# SMARTCONTROL.net
KiCad netlist of a schematic drawn in EAGLE
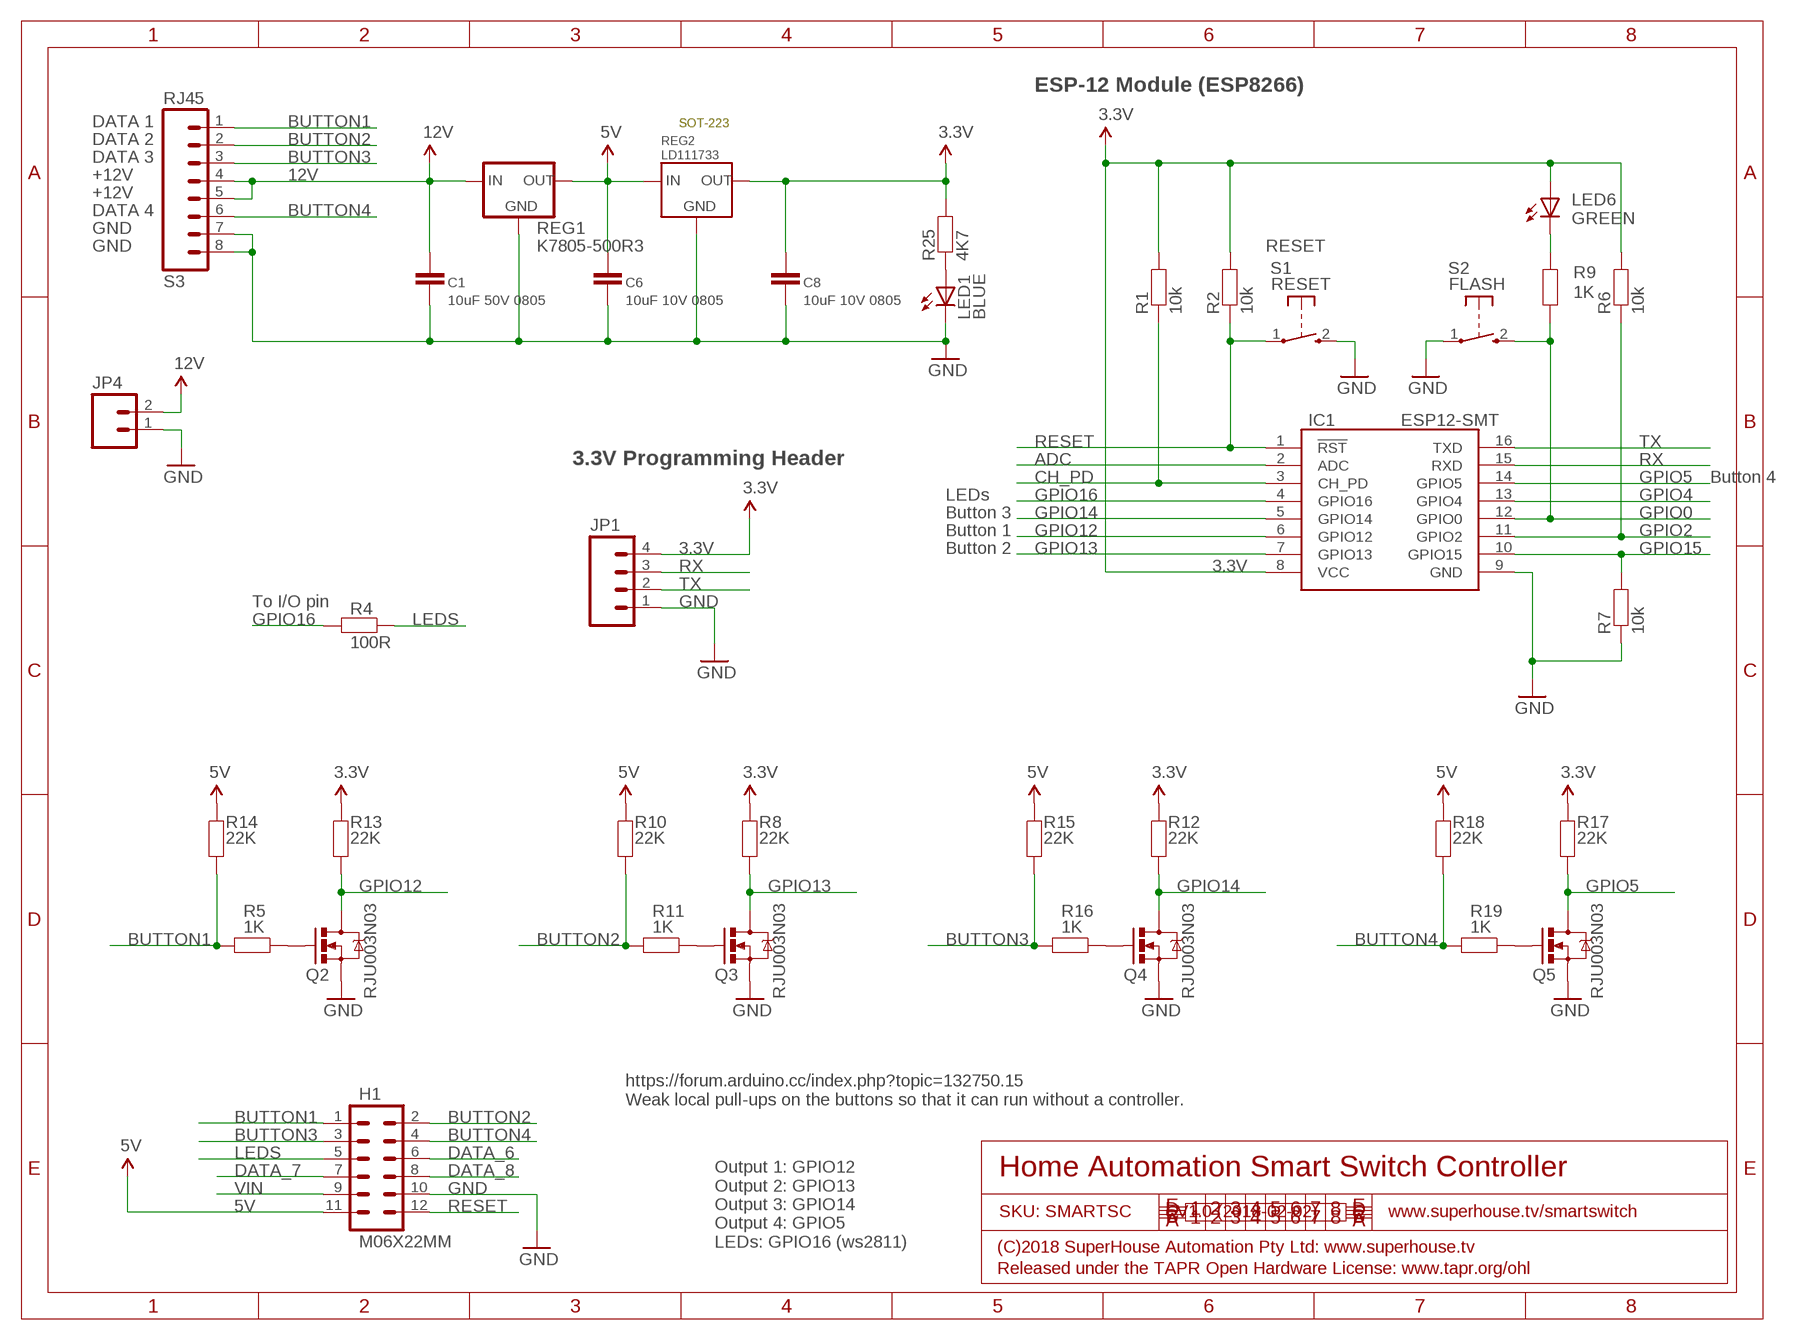
[diagram p0: schematic, sheet 1]

(export (version "E")
  (design (tool "Eeschema 10.0.6"))
  (components
    (comp (ref "C1")
      (value "10uF 50V 0805")
      (footprint "eagle-import:C0805")
      (libsource (lib "eagle-import") (part "CAP0805"))
    )
    (comp (ref "C6")
      (value "10uF 10V 0805")
      (footprint "eagle-import:C0805")
      (libsource (lib "eagle-import") (part "CAP0805"))
    )
    (comp (ref "C8")
      (value "10uF 10V 0805")
      (footprint "eagle-import:C0805")
      (libsource (lib "eagle-import") (part "CAP0805"))
    )
    (comp (ref "H1")
      (value "M06X22MM")
      (footprint "eagle-import:2X6-2MM")
      (libsource (lib "eagle-import") (part "M06X22MM"))
    )
    (comp (ref "IC1")
      (value "ESP12-SMT")
      (footprint "eagle-import:ESP12")
      (libsource (lib "eagle-import") (part "ESP12-SMT"))
    )
    (comp (ref "JP1")
      (value "M04PTH")
      (footprint "eagle-import:1X04")
      (libsource (lib "eagle-import") (part "M04PTH"))
    )
    (comp (ref "JP4")
      (value "M023.5MM")
      (footprint "eagle-import:SCREWTERMINAL-3.5MM-2")
      (libsource (lib "eagle-import") (part "M023.5MM"))
    )
    (comp (ref "LED1")
      (value "BLUE")
      (footprint "eagle-import:LED-0603")
      (libsource (lib "eagle-import") (part "LED0603"))
    )
    (comp (ref "LED6")
      (value "GREEN")
      (footprint "eagle-import:LED-0603")
      (libsource (lib "eagle-import") (part "LED0603"))
    )
    (comp (ref "Q2")
      (value "RJU003N03")
      (footprint "eagle-import:SOT32-3")
      (libsource (lib "eagle-import") (part "MOSFET-NCHANNEL-323"))
    )
    (comp (ref "Q3")
      (value "RJU003N03")
      (footprint "eagle-import:SOT32-3")
      (libsource (lib "eagle-import") (part "MOSFET-NCHANNEL-323"))
    )
    (comp (ref "Q4")
      (value "RJU003N03")
      (footprint "eagle-import:SOT32-3")
      (libsource (lib "eagle-import") (part "MOSFET-NCHANNEL-323"))
    )
    (comp (ref "Q5")
      (value "RJU003N03")
      (footprint "eagle-import:SOT32-3")
      (libsource (lib "eagle-import") (part "MOSFET-NCHANNEL-323"))
    )
    (comp (ref "R1")
      (value "10k")
      (footprint "eagle-import:R0603")
      (libsource (lib "eagle-import") (part "RESISTOR0603"))
    )
    (comp (ref "R2")
      (value "10k")
      (footprint "eagle-import:R0603")
      (libsource (lib "eagle-import") (part "RESISTOR0603"))
    )
    (comp (ref "R4")
      (value "100R")
      (footprint "eagle-import:R0603")
      (libsource (lib "eagle-import") (part "RESISTOR0603"))
    )
    (comp (ref "R5")
      (value "1K")
      (footprint "eagle-import:R0603")
      (libsource (lib "eagle-import") (part "RESISTOR0603"))
    )
    (comp (ref "R6")
      (value "10k")
      (footprint "eagle-import:R0603")
      (libsource (lib "eagle-import") (part "RESISTOR0603"))
    )
    (comp (ref "R7")
      (value "10k")
      (footprint "eagle-import:R0603")
      (libsource (lib "eagle-import") (part "RESISTOR0603"))
    )
    (comp (ref "R8")
      (value "22K")
      (footprint "eagle-import:R0603")
      (libsource (lib "eagle-import") (part "RESISTOR0603"))
    )
    (comp (ref "R9")
      (value "1K")
      (footprint "eagle-import:R0603")
      (libsource (lib "eagle-import") (part "RESISTOR0603"))
    )
    (comp (ref "R10")
      (value "22K")
      (footprint "eagle-import:R0603")
      (libsource (lib "eagle-import") (part "RESISTOR0603"))
    )
    (comp (ref "R11")
      (value "1K")
      (footprint "eagle-import:R0603")
      (libsource (lib "eagle-import") (part "RESISTOR0603"))
    )
    (comp (ref "R12")
      (value "22K")
      (footprint "eagle-import:R0603")
      (libsource (lib "eagle-import") (part "RESISTOR0603"))
    )
    (comp (ref "R13")
      (value "22K")
      (footprint "eagle-import:R0603")
      (libsource (lib "eagle-import") (part "RESISTOR0603"))
    )
    (comp (ref "R14")
      (value "22K")
      (footprint "eagle-import:R0603")
      (libsource (lib "eagle-import") (part "RESISTOR0603"))
    )
    (comp (ref "R15")
      (value "22K")
      (footprint "eagle-import:R0603")
      (libsource (lib "eagle-import") (part "RESISTOR0603"))
    )
    (comp (ref "R16")
      (value "1K")
      (footprint "eagle-import:R0603")
      (libsource (lib "eagle-import") (part "RESISTOR0603"))
    )
    (comp (ref "R17")
      (value "22K")
      (footprint "eagle-import:R0603")
      (libsource (lib "eagle-import") (part "RESISTOR0603"))
    )
    (comp (ref "R18")
      (value "22K")
      (footprint "eagle-import:R0603")
      (libsource (lib "eagle-import") (part "RESISTOR0603"))
    )
    (comp (ref "R19")
      (value "1K")
      (footprint "eagle-import:R0603")
      (libsource (lib "eagle-import") (part "RESISTOR0603"))
    )
    (comp (ref "R25")
      (value "4K7")
      (footprint "eagle-import:R0603")
      (libsource (lib "eagle-import") (part "RESISTOR0603"))
    )
    (comp (ref "REG1")
      (value "K7805-500R3")
      (footprint "eagle-import:K78XX-500R3")
      (libsource (lib "eagle-import") (part "K78XX-500R3"))
    )
    (comp (ref "REG2")
      (value "LD111733")
      (footprint "eagle-import:SOT-223")
      (libsource (lib "eagle-import") (part "LD1117"))
    )
    (comp (ref "S1")
      (value "RESET")
      (footprint "eagle-import:TACTILE_SMD_3X4X2")
      (libsource (lib "eagle-import") (part "TAC_SWITCH_2PINSMT"))
    )
    (comp (ref "S2")
      (value "FLASH")
      (footprint "eagle-import:TACTILE_SMD_3X4X2")
      (libsource (lib "eagle-import") (part "TAC_SWITCH_2PINSMT"))
    )
    (comp (ref "S3")
      (value "RJ45")
      (footprint "eagle-import:RJ45")
      (libsource (lib "eagle-import") (part "RJ45"))
    )
  )
  (nets
    (net (code "1") (name "/ADC") (class "Default")
      (node (ref "IC1") (pin "2") (pinfunction "ADC_2") (pintype "input"))
    )
    (net (code "2") (name "/BUTTON1") (class "Default")
      (node (ref "H1") (pin "1") (pinfunction "1_1") (pintype "passive"))
      (node (ref "R14") (pin "1") (pinfunction "1_1") (pintype "passive"))
      (node (ref "R5") (pin "2") (pinfunction "2_2") (pintype "passive"))
      (node (ref "S3") (pin "1") (pinfunction "1_1") (pintype "passive"))
    )
    (net (code "3") (name "/BUTTON2") (class "Default")
      (node (ref "H1") (pin "2") (pinfunction "2_2") (pintype "passive"))
      (node (ref "R10") (pin "1") (pinfunction "1_1") (pintype "passive"))
      (node (ref "R11") (pin "2") (pinfunction "2_2") (pintype "passive"))
      (node (ref "S3") (pin "2") (pinfunction "2_2") (pintype "passive"))
    )
    (net (code "4") (name "/BUTTON3") (class "Default")
      (node (ref "H1") (pin "3") (pinfunction "3_3") (pintype "passive"))
      (node (ref "R15") (pin "1") (pinfunction "1_1") (pintype "passive"))
      (node (ref "R16") (pin "2") (pinfunction "2_2") (pintype "passive"))
      (node (ref "S3") (pin "3") (pinfunction "3_3") (pintype "passive"))
    )
    (net (code "5") (name "/BUTTON4") (class "Default")
      (node (ref "H1") (pin "4") (pinfunction "4_4") (pintype "passive"))
      (node (ref "R18") (pin "1") (pinfunction "1_1") (pintype "passive"))
      (node (ref "R19") (pin "2") (pinfunction "2_2") (pintype "passive"))
      (node (ref "S3") (pin "6") (pinfunction "6_6") (pintype "passive"))
    )
    (net (code "6") (name "/CH_PD") (class "Default")
      (node (ref "IC1") (pin "3") (pinfunction "CH_PD_3") (pintype "input"))
      (node (ref "R1") (pin "1") (pinfunction "1_1") (pintype "passive"))
    )
    (net (code "7") (name "/DATA_6") (class "Default")
      (node (ref "H1") (pin "6") (pinfunction "6_6") (pintype "passive"))
    )
    (net (code "8") (name "/DATA_7") (class "Default")
      (node (ref "H1") (pin "7") (pinfunction "7_7") (pintype "passive"))
    )
    (net (code "9") (name "/DATA_8") (class "Default")
      (node (ref "H1") (pin "8") (pinfunction "8_8") (pintype "passive"))
    )
    (net (code "10") (name "/GPIO0") (class "Default")
      (node (ref "IC1") (pin "12") (pinfunction "GPIO0_12") (pintype "bidirectional"))
      (node (ref "R9") (pin "2") (pinfunction "2_2") (pintype "passive"))
      (node (ref "S2") (pin "2") (pinfunction "S_2") (pintype "passive"))
    )
    (net (code "11") (name "/GPIO2") (class "Default")
      (node (ref "IC1") (pin "11") (pinfunction "GPIO2_11") (pintype "bidirectional"))
      (node (ref "R6") (pin "1") (pinfunction "1_1") (pintype "passive"))
    )
    (net (code "12") (name "/GPIO4") (class "Default")
      (node (ref "IC1") (pin "13") (pinfunction "GPIO4_13") (pintype "bidirectional"))
    )
    (net (code "13") (name "/GPIO5") (class "Default")
      (node (ref "IC1") (pin "14") (pinfunction "GPIO5_14") (pintype "bidirectional"))
      (node (ref "Q5") (pin "3") (pinfunction "D_3") (pintype "passive"))
      (node (ref "R17") (pin "1") (pinfunction "1_1") (pintype "passive"))
    )
    (net (code "14") (name "/GPIO12") (class "Default")
      (node (ref "IC1") (pin "6") (pinfunction "GPIO12_6") (pintype "bidirectional"))
      (node (ref "Q2") (pin "3") (pinfunction "D_3") (pintype "passive"))
      (node (ref "R13") (pin "1") (pinfunction "1_1") (pintype "passive"))
    )
    (net (code "15") (name "/GPIO13") (class "Default")
      (node (ref "IC1") (pin "7") (pinfunction "GPIO13_7") (pintype "bidirectional"))
      (node (ref "Q3") (pin "3") (pinfunction "D_3") (pintype "passive"))
      (node (ref "R8") (pin "1") (pinfunction "1_1") (pintype "passive"))
    )
    (net (code "16") (name "/GPIO14") (class "Default")
      (node (ref "IC1") (pin "5") (pinfunction "GPIO14_5") (pintype "bidirectional"))
      (node (ref "Q4") (pin "3") (pinfunction "D_3") (pintype "passive"))
      (node (ref "R12") (pin "1") (pinfunction "1_1") (pintype "passive"))
    )
    (net (code "17") (name "/GPIO15") (class "Default")
      (node (ref "IC1") (pin "10") (pinfunction "GPIO15_10") (pintype "bidirectional"))
      (node (ref "R7") (pin "2") (pinfunction "2_2") (pintype "passive"))
    )
    (net (code "18") (name "/GPIO16") (class "Default")
      (node (ref "IC1") (pin "4") (pinfunction "GPIO16_4") (pintype "bidirectional"))
      (node (ref "R4") (pin "2") (pinfunction "2_2") (pintype "passive"))
    )
    (net (code "19") (name "/LEDS") (class "Default")
      (node (ref "H1") (pin "5") (pinfunction "5_5") (pintype "passive"))
      (node (ref "R4") (pin "1") (pinfunction "1_1") (pintype "passive"))
    )
    (net (code "20") (name "/RESET") (class "Default")
      (node (ref "H1") (pin "12") (pinfunction "12_12") (pintype "passive"))
      (node (ref "IC1") (pin "1") (pinfunction "~{RST}_1") (pintype "bidirectional"))
      (node (ref "R2") (pin "1") (pinfunction "1_1") (pintype "passive"))
      (node (ref "S1") (pin "1") (pinfunction "P_1") (pintype "passive"))
    )
    (net (code "21") (name "/RX") (class "Default")
      (node (ref "IC1") (pin "15") (pinfunction "RXD_15") (pintype "input"))
      (node (ref "JP1") (pin "3") (pinfunction "3_3") (pintype "passive"))
    )
    (net (code "22") (name "/TX") (class "Default")
      (node (ref "IC1") (pin "16") (pinfunction "TXD_16") (pintype "output"))
      (node (ref "JP1") (pin "2") (pinfunction "2_2") (pintype "passive"))
    )
    (net (code "23") (name "/VIN") (class "Default")
      (node (ref "H1") (pin "9") (pinfunction "9_9") (pintype "passive"))
    )
    (net (code "24") (name "3.3V") (class "Default")
      (node (ref "C8") (pin "1") (pinfunction "1_1") (pintype "passive"))
      (node (ref "IC1") (pin "8") (pinfunction "VCC_8") (pintype "power_in"))
      (node (ref "JP1") (pin "4") (pinfunction "4_4") (pintype "passive"))
      (node (ref "LED6") (pin "A") (pinfunction "A_A") (pintype "passive"))
      (node (ref "R1") (pin "2") (pinfunction "2_2") (pintype "passive"))
      (node (ref "R12") (pin "2") (pinfunction "2_2") (pintype "passive"))
      (node (ref "R13") (pin "2") (pinfunction "2_2") (pintype "passive"))
      (node (ref "R17") (pin "2") (pinfunction "2_2") (pintype "passive"))
      (node (ref "R2") (pin "2") (pinfunction "2_2") (pintype "passive"))
      (node (ref "R25") (pin "2") (pinfunction "2_2") (pintype "passive"))
      (node (ref "R6") (pin "2") (pinfunction "2_2") (pintype "passive"))
      (node (ref "R8") (pin "2") (pinfunction "2_2") (pintype "passive"))
      (node (ref "REG2") (pin "2") (pinfunction "OUT_2") (pintype "power_in"))
      (node (ref "REG2") (pin "4") (pinfunction "OUT_4") (pintype "power_in"))
    )
    (net (code "25") (name "5V") (class "Default")
      (node (ref "C6") (pin "1") (pinfunction "1_1") (pintype "passive"))
      (node (ref "H1") (pin "11") (pinfunction "11_11") (pintype "passive"))
      (node (ref "R10") (pin "2") (pinfunction "2_2") (pintype "passive"))
      (node (ref "R14") (pin "2") (pinfunction "2_2") (pintype "passive"))
      (node (ref "R15") (pin "2") (pinfunction "2_2") (pintype "passive"))
      (node (ref "R18") (pin "2") (pinfunction "2_2") (pintype "passive"))
      (node (ref "REG1") (pin "3") (pinfunction "OUT_3") (pintype "output"))
      (node (ref "REG2") (pin "3") (pinfunction "IN_3") (pintype "input"))
    )
    (net (code "26") (name "12V") (class "Default")
      (node (ref "C1") (pin "1") (pinfunction "1_1") (pintype "passive"))
      (node (ref "JP4") (pin "2") (pinfunction "2_2") (pintype "passive"))
      (node (ref "REG1") (pin "1") (pinfunction "IN_1") (pintype "input"))
      (node (ref "S3") (pin "4") (pinfunction "4_4") (pintype "passive"))
      (node (ref "S3") (pin "5") (pinfunction "5_5") (pintype "passive"))
    )
    (net (code "27") (name "GND") (class "Default")
      (node (ref "C1") (pin "2") (pinfunction "2_2") (pintype "passive"))
      (node (ref "C6") (pin "2") (pinfunction "2_2") (pintype "passive"))
      (node (ref "C8") (pin "2") (pinfunction "2_2") (pintype "passive"))
      (node (ref "H1") (pin "10") (pinfunction "10_10") (pintype "passive"))
      (node (ref "IC1") (pin "9") (pinfunction "GND_9") (pintype "power_in"))
      (node (ref "JP1") (pin "1") (pinfunction "1_1") (pintype "passive"))
      (node (ref "JP4") (pin "1") (pinfunction "1_1") (pintype "passive"))
      (node (ref "LED1") (pin "C") (pinfunction "C_C") (pintype "passive"))
      (node (ref "Q2") (pin "2") (pinfunction "S_2") (pintype "passive"))
      (node (ref "Q3") (pin "2") (pinfunction "S_2") (pintype "passive"))
      (node (ref "Q4") (pin "2") (pinfunction "S_2") (pintype "passive"))
      (node (ref "Q5") (pin "2") (pinfunction "S_2") (pintype "passive"))
      (node (ref "R7") (pin "1") (pinfunction "1_1") (pintype "passive"))
      (node (ref "REG1") (pin "2") (pinfunction "GND_2") (pintype "input"))
      (node (ref "REG2") (pin "1") (pinfunction "GND_1") (pintype "input"))
      (node (ref "S1") (pin "2") (pinfunction "S_2") (pintype "passive"))
      (node (ref "S2") (pin "1") (pinfunction "P_1") (pintype "passive"))
      (node (ref "S3") (pin "7") (pinfunction "7_7") (pintype "passive"))
      (node (ref "S3") (pin "8") (pinfunction "8_8") (pintype "passive"))
    )
    (net (code "28") (name "Net-(LED1-PadA)") (class "Default")
      (node (ref "LED1") (pin "A") (pinfunction "A_A") (pintype "passive"))
      (node (ref "R25") (pin "1") (pinfunction "1_1") (pintype "passive"))
    )
    (net (code "29") (name "Net-(LED6-PadC)") (class "Default")
      (node (ref "LED6") (pin "C") (pinfunction "C_C") (pintype "passive"))
      (node (ref "R9") (pin "1") (pinfunction "1_1") (pintype "passive"))
    )
    (net (code "30") (name "Net-(Q2-G)") (class "Default")
      (node (ref "Q2") (pin "1") (pinfunction "G_1") (pintype "passive"))
      (node (ref "R5") (pin "1") (pinfunction "1_1") (pintype "passive"))
    )
    (net (code "31") (name "Net-(Q3-G)") (class "Default")
      (node (ref "Q3") (pin "1") (pinfunction "G_1") (pintype "passive"))
      (node (ref "R11") (pin "1") (pinfunction "1_1") (pintype "passive"))
    )
    (net (code "32") (name "Net-(Q4-G)") (class "Default")
      (node (ref "Q4") (pin "1") (pinfunction "G_1") (pintype "passive"))
      (node (ref "R16") (pin "1") (pinfunction "1_1") (pintype "passive"))
    )
    (net (code "33") (name "Net-(Q5-G)") (class "Default")
      (node (ref "Q5") (pin "1") (pinfunction "G_1") (pintype "passive"))
      (node (ref "R19") (pin "1") (pinfunction "1_1") (pintype "passive"))
    )
  )
)
